# RF_Front_End.net
KiCad netlist of a schematic drawn in Altium Designer
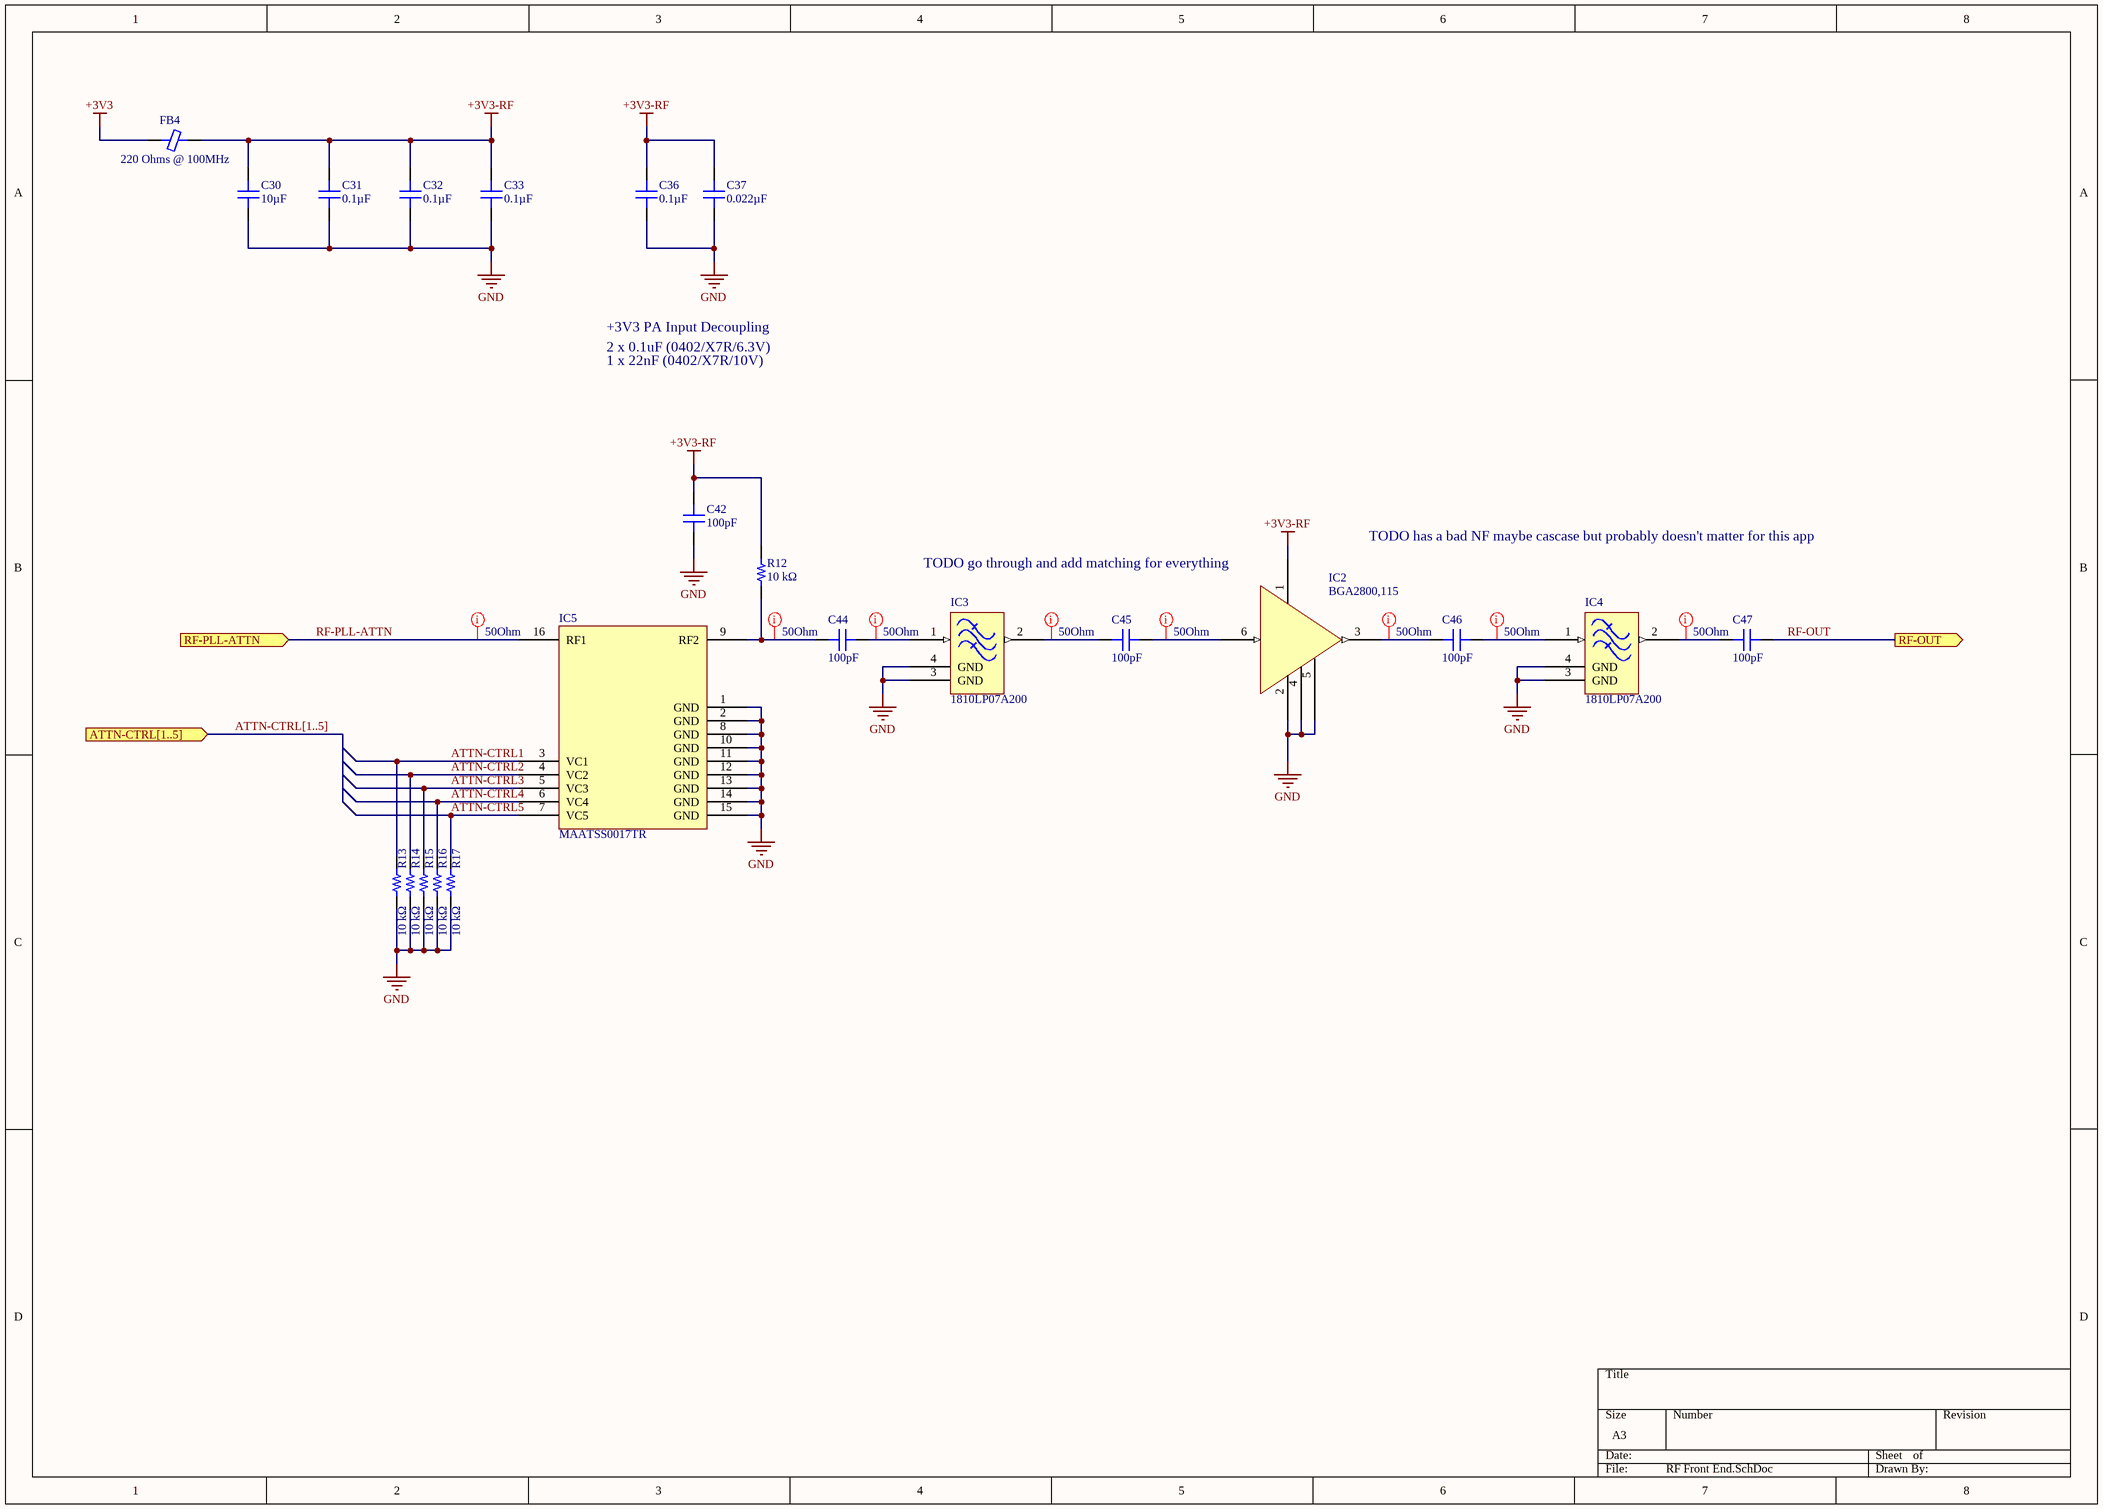
[diagram p0: RF Front End.SchDoc]

(export (version "E")
  (design (tool "Eeschema 10.0.6"))
  (components
    (comp (ref "C30")
      (value "10µF")
      (footprint "CAP 0805_2012")
      (description "CAP CER 10UF 6.3V X5R 0805")
      (fields (field (name "PART NUMBER") "08056D106KAT4A") (field (name "MANUFACTURER") "AVX Corporation"))
      (libsource (lib "Generic Altium Database") (part "Capacitor"))
    )
    (comp (ref "C31")
      (value "0.1µF")
      (footprint "CAP 0402_1005")
      (description "CAP CER 0.1UF 6.3V X7R 0402")
      (fields
        (field (name "PART NUMBER") "0402B104K6R3CT")
        (field (name "MANUFACTURER") "Walsin Technology Corporation")
      )
      (libsource (lib "Generic Altium Database") (part "Capacitor"))
    )
    (comp (ref "C32")
      (value "0.1µF")
      (footprint "CAP 0402_1005")
      (description "CAP CER 0.1UF 6.3V X7R 0402")
      (fields
        (field (name "PART NUMBER") "0402B104K6R3CT")
        (field (name "MANUFACTURER") "Walsin Technology Corporation")
      )
      (libsource (lib "Generic Altium Database") (part "Capacitor"))
    )
    (comp (ref "C33")
      (value "0.1µF")
      (footprint "CAP 0402_1005")
      (description "CAP CER 0.1UF 6.3V X7R 0402")
      (fields
        (field (name "PART NUMBER") "0402B104K6R3CT")
        (field (name "MANUFACTURER") "Walsin Technology Corporation")
      )
      (libsource (lib "Generic Altium Database") (part "Capacitor"))
    )
    (comp (ref "C36")
      (value "0.1µF")
      (footprint "CAP 0402_1005")
      (description "CAP CER 0.1UF 6.3V X7R 0402")
      (fields
        (field (name "PART NUMBER") "0402B104K6R3CT")
        (field (name "MANUFACTURER") "Walsin Technology Corporation")
      )
      (libsource (lib "Generic Altium Database") (part "Capacitor"))
    )
    (comp (ref "C37")
      (value "0.022µF")
      (footprint "CAP 0402_1005")
      (description "CAP CER 0402 22NF 16V X7R 10%")
      (fields (field (name "PART NUMBER") "C0402C223K4RECAUTO") (field (name "MANUFACTURER") "KEMET"))
      (libsource (lib "Generic Altium Database") (part "Capacitor"))
    )
    (comp (ref "C42")
      (value "100pF")
      (footprint "CAP 0402_1005")
      (description "CAP CER 100PF 25V X7R 0402")
      (fields (field (name "PART NUMBER") "04023C101KAT2A") (field (name "MANUFACTURER") "AVX Corporation"))
      (libsource (lib "Generic Altium Database") (part "Capacitor"))
    )
    (comp (ref "C44")
      (value "100pF")
      (footprint "CAP 0402_1005 RF")
      (description "CAP CER 100PF 25V C0G/NP0 0402")
      (fields (field (name "PART NUMBER") "CBR04C101F3GAC") (field (name "MANUFACTURER") "KEMET"))
      (libsource (lib "Generic Altium Database") (part "Capacitor"))
    )
    (comp (ref "C45")
      (value "100pF")
      (footprint "CAP 0402_1005 RF")
      (description "CAP CER 100PF 25V C0G/NP0 0402")
      (fields (field (name "PART NUMBER") "CBR04C101F3GAC") (field (name "MANUFACTURER") "KEMET"))
      (libsource (lib "Generic Altium Database") (part "Capacitor"))
    )
    (comp (ref "C46")
      (value "100pF")
      (footprint "CAP 0402_1005 RF")
      (description "CAP CER 100PF 25V C0G/NP0 0402")
      (fields (field (name "PART NUMBER") "CBR04C101F3GAC") (field (name "MANUFACTURER") "KEMET"))
      (libsource (lib "Generic Altium Database") (part "Capacitor"))
    )
    (comp (ref "C47")
      (value "100pF")
      (footprint "CAP 0402_1005 RF")
      (description "CAP CER 100PF 25V C0G/NP0 0402")
      (fields (field (name "PART NUMBER") "CBR04C101F3GAC") (field (name "MANUFACTURER") "KEMET"))
      (libsource (lib "Generic Altium Database") (part "Capacitor"))
    )
    (comp (ref "FB4")
      (value "220 Ohms @ 100MHz")
      (footprint "FER 0402_1005")
      (description "EMI BEAD FILETER")
      (fields
        (field (name "PART NUMBER") "BBPY00100505221Y00")
        (field (name "MANUFACTURER") "Chilisin Electronics")
      )
      (libsource (lib "Generic Altium Database") (part "Ferrite Chip"))
    )
    (comp (ref "IC2")
      (value "BGA2800,115")
      (footprint "NXP SOT-363")
      (description "IC RF AMP GP 0HZ-2.2GHZ 6TSSOP")
      (fields (field (name "MANUFACTURER") "NXP USA Inc."))
      (libsource (lib "Generic Altium Database") (part "NXP BGA2800"))
    )
    (comp (ref "IC3")
      (value "1810LP07A200")
      (footprint "JOHANSON 0402 4PAD")
      (description "RF FILTER LOW PASS 1.81GHZ 0402")
      (fields (field (name "MANUFACTURER") "Johanson Technology Inc."))
      (libsource (lib "Generic Altium Database") (part "JOHANSON 4PAD FILTER"))
    )
    (comp (ref "IC4")
      (value "1810LP07A200")
      (footprint "JOHANSON 0402 4PAD")
      (description "RF FILTER LOW PASS 1.81GHZ 0402")
      (fields (field (name "MANUFACTURER") "Johanson Technology Inc."))
      (libsource (lib "Generic Altium Database") (part "JOHANSON 4PAD FILTER"))
    )
    (comp (ref "IC5")
      (value "MAATSS0017TR")
      (footprint "TI TSSOP-16 PW")
      (description "RF Attenuators 15.5dB 400MHz ~ 2.5GHz 50 Ohms 16-LSSOP (0.154\", 3.90mm Width)")
      (fields (field (name "MANUFACTURER") "MACOM Technology Solutions"))
      (libsource (lib "Generic Altium Database") (part "MACOM MAATSS0017TR"))
    )
    (comp (ref "R12")
      (value "10 kΩ")
      (footprint "RES 0402_1005")
      (description "RES 10 KOHM 1% 1/16W 0402")
      (fields (field (name "PART NUMBER") "ASC0402-10KF1") (field (name "MANUFACTURER") "Riedon"))
      (libsource (lib "Generic Altium Database") (part "Resistor"))
    )
    (comp (ref "R13")
      (value "10 kΩ")
      (footprint "RES 0402_1005")
      (description "RES 10 KOHM 1% 1/16W 0402")
      (fields (field (name "PART NUMBER") "ASC0402-10KF1") (field (name "MANUFACTURER") "Riedon"))
      (libsource (lib "Generic Altium Database") (part "Resistor"))
    )
    (comp (ref "R14")
      (value "10 kΩ")
      (footprint "RES 0402_1005")
      (description "RES 10 KOHM 1% 1/16W 0402")
      (fields (field (name "PART NUMBER") "ASC0402-10KF1") (field (name "MANUFACTURER") "Riedon"))
      (libsource (lib "Generic Altium Database") (part "Resistor"))
    )
    (comp (ref "R15")
      (value "10 kΩ")
      (footprint "RES 0402_1005")
      (description "RES 10 KOHM 1% 1/16W 0402")
      (fields (field (name "PART NUMBER") "ASC0402-10KF1") (field (name "MANUFACTURER") "Riedon"))
      (libsource (lib "Generic Altium Database") (part "Resistor"))
    )
    (comp (ref "R16")
      (value "10 kΩ")
      (footprint "RES 0402_1005")
      (description "RES 10 KOHM 1% 1/16W 0402")
      (fields (field (name "PART NUMBER") "ASC0402-10KF1") (field (name "MANUFACTURER") "Riedon"))
      (libsource (lib "Generic Altium Database") (part "Resistor"))
    )
    (comp (ref "R17")
      (value "10 kΩ")
      (footprint "RES 0402_1005")
      (description "RES 10 KOHM 1% 1/16W 0402")
      (fields (field (name "PART NUMBER") "ASC0402-10KF1") (field (name "MANUFACTURER") "Riedon"))
      (libsource (lib "Generic Altium Database") (part "Resistor"))
    )
  )
  (nets
    (net (code "1") (name "+3V3") (class "Default")
      (node (ref "FB4") (pin "2") (pinfunction "2_2") (pintype "passive"))
    )
    (net (code "2") (name "+3V3-RF") (class "Default")
      (node (ref "C30") (pin "2") (pinfunction "2_2") (pintype "passive"))
      (node (ref "C31") (pin "2") (pinfunction "2_2") (pintype "passive"))
      (node (ref "C32") (pin "2") (pinfunction "2_2") (pintype "passive"))
      (node (ref "C33") (pin "2") (pinfunction "2_2") (pintype "passive"))
      (node (ref "C36") (pin "2") (pinfunction "2_2") (pintype "passive"))
      (node (ref "C37") (pin "1") (pinfunction "1_1") (pintype "passive"))
      (node (ref "C42") (pin "1") (pinfunction "1_1") (pintype "passive"))
      (node (ref "FB4") (pin "1") (pinfunction "1_1") (pintype "passive"))
      (node (ref "IC2") (pin "1") (pinfunction "VCC_1") (pintype "power_in"))
      (node (ref "R12") (pin "2") (pinfunction "2_2") (pintype "passive"))
    )
    (net (code "3") (name "/ATTN-CTRL1") (class "Default")
      (node (ref "IC5") (pin "3") (pinfunction "VC1_3") (pintype "passive"))
      (node (ref "R13") (pin "2") (pinfunction "2_2") (pintype "passive"))
    )
    (net (code "4") (name "/ATTN-CTRL2") (class "Default")
      (node (ref "IC5") (pin "4") (pinfunction "VC2_4") (pintype "passive"))
      (node (ref "R14") (pin "2") (pinfunction "2_2") (pintype "passive"))
    )
    (net (code "5") (name "/ATTN-CTRL3") (class "Default")
      (node (ref "IC5") (pin "5") (pinfunction "VC3_5") (pintype "passive"))
      (node (ref "R15") (pin "2") (pinfunction "2_2") (pintype "passive"))
    )
    (net (code "6") (name "/ATTN-CTRL4") (class "Default")
      (node (ref "IC5") (pin "6") (pinfunction "VC4_6") (pintype "passive"))
      (node (ref "R16") (pin "2") (pinfunction "2_2") (pintype "passive"))
    )
    (net (code "7") (name "/ATTN-CTRL5") (class "Default")
      (node (ref "IC5") (pin "7") (pinfunction "VC5_7") (pintype "passive"))
      (node (ref "R17") (pin "2") (pinfunction "2_2") (pintype "passive"))
    )
    (net (code "9") (name "/RF-OUT") (class "Default")
      (node (ref "C47") (pin "2") (pinfunction "2_2") (pintype "passive"))
    )
    (net (code "10") (name "/RF-PLL-ATTN") (class "Default")
      (node (ref "IC5") (pin "16") (pinfunction "RF1_16") (pintype "passive"))
    )
    (net (code "11") (name "GND") (class "Default")
      (node (ref "C30") (pin "1") (pinfunction "1_1") (pintype "passive"))
      (node (ref "C31") (pin "1") (pinfunction "1_1") (pintype "passive"))
      (node (ref "C32") (pin "1") (pinfunction "1_1") (pintype "passive"))
      (node (ref "C33") (pin "1") (pinfunction "1_1") (pintype "passive"))
      (node (ref "C36") (pin "1") (pinfunction "1_1") (pintype "passive"))
      (node (ref "C37") (pin "2") (pinfunction "2_2") (pintype "passive"))
      (node (ref "C42") (pin "2") (pinfunction "2_2") (pintype "passive"))
      (node (ref "IC2") (pin "2") (pinfunction "GND_2") (pintype "power_in"))
      (node (ref "IC2") (pin "4") (pinfunction "GND_4") (pintype "power_in"))
      (node (ref "IC2") (pin "5") (pinfunction "GND_5") (pintype "power_in"))
      (node (ref "IC3") (pin "3") (pinfunction "GND_3") (pintype "passive"))
      (node (ref "IC3") (pin "4") (pinfunction "GND_4") (pintype "passive"))
      (node (ref "IC4") (pin "3") (pinfunction "GND_3") (pintype "passive"))
      (node (ref "IC4") (pin "4") (pinfunction "GND_4") (pintype "passive"))
      (node (ref "IC5") (pin "1") (pinfunction "GND_1") (pintype "passive"))
      (node (ref "IC5") (pin "10") (pinfunction "GND_10") (pintype "passive"))
      (node (ref "IC5") (pin "11") (pinfunction "GND_11") (pintype "passive"))
      (node (ref "IC5") (pin "12") (pinfunction "GND_12") (pintype "passive"))
      (node (ref "IC5") (pin "13") (pinfunction "GND_13") (pintype "passive"))
      (node (ref "IC5") (pin "14") (pinfunction "GND_14") (pintype "passive"))
      (node (ref "IC5") (pin "15") (pinfunction "GND_15") (pintype "passive"))
      (node (ref "IC5") (pin "2") (pinfunction "GND_2") (pintype "passive"))
      (node (ref "IC5") (pin "8") (pinfunction "GND_8") (pintype "passive"))
      (node (ref "R13") (pin "1") (pinfunction "1_1") (pintype "passive"))
      (node (ref "R14") (pin "1") (pinfunction "1_1") (pintype "passive"))
      (node (ref "R15") (pin "1") (pinfunction "1_1") (pintype "passive"))
      (node (ref "R16") (pin "1") (pinfunction "1_1") (pintype "passive"))
      (node (ref "R17") (pin "1") (pinfunction "1_1") (pintype "passive"))
    )
    (net (code "12") (name "Net-(IC2-RFIN)") (class "Default")
      (node (ref "C45") (pin "2") (pinfunction "2_2") (pintype "passive"))
      (node (ref "IC2") (pin "6") (pinfunction "RFIN_6") (pintype "input"))
    )
    (net (code "13") (name "Net-(IC2-RFOUT)") (class "Default")
      (node (ref "C46") (pin "1") (pinfunction "1_1") (pintype "passive"))
      (node (ref "IC2") (pin "3") (pinfunction "RFOUT_3") (pintype "output"))
    )
    (net (code "14") (name "Net-(IC3-IN)") (class "Default")
      (node (ref "C44") (pin "2") (pinfunction "2_2") (pintype "passive"))
      (node (ref "IC3") (pin "1") (pinfunction "IN_1") (pintype "input"))
    )
    (net (code "15") (name "Net-(IC3-OUT)") (class "Default")
      (node (ref "C45") (pin "1") (pinfunction "1_1") (pintype "passive"))
      (node (ref "IC3") (pin "2") (pinfunction "OUT_2") (pintype "output"))
    )
    (net (code "16") (name "Net-(IC4-IN)") (class "Default")
      (node (ref "C46") (pin "2") (pinfunction "2_2") (pintype "passive"))
      (node (ref "IC4") (pin "1") (pinfunction "IN_1") (pintype "input"))
    )
    (net (code "17") (name "Net-(IC4-OUT)") (class "Default")
      (node (ref "C47") (pin "1") (pinfunction "1_1") (pintype "passive"))
      (node (ref "IC4") (pin "2") (pinfunction "OUT_2") (pintype "output"))
    )
    (net (code "18") (name "Net-(IC5-RF2)") (class "Default")
      (node (ref "C44") (pin "1") (pinfunction "1_1") (pintype "passive"))
      (node (ref "IC5") (pin "9") (pinfunction "RF2_9") (pintype "passive"))
      (node (ref "R12") (pin "1") (pinfunction "1_1") (pintype "passive"))
    )
  )
)
